# 2CH_PM_Simulator.net
KiCad netlist of a schematic drawn in Altium Designer
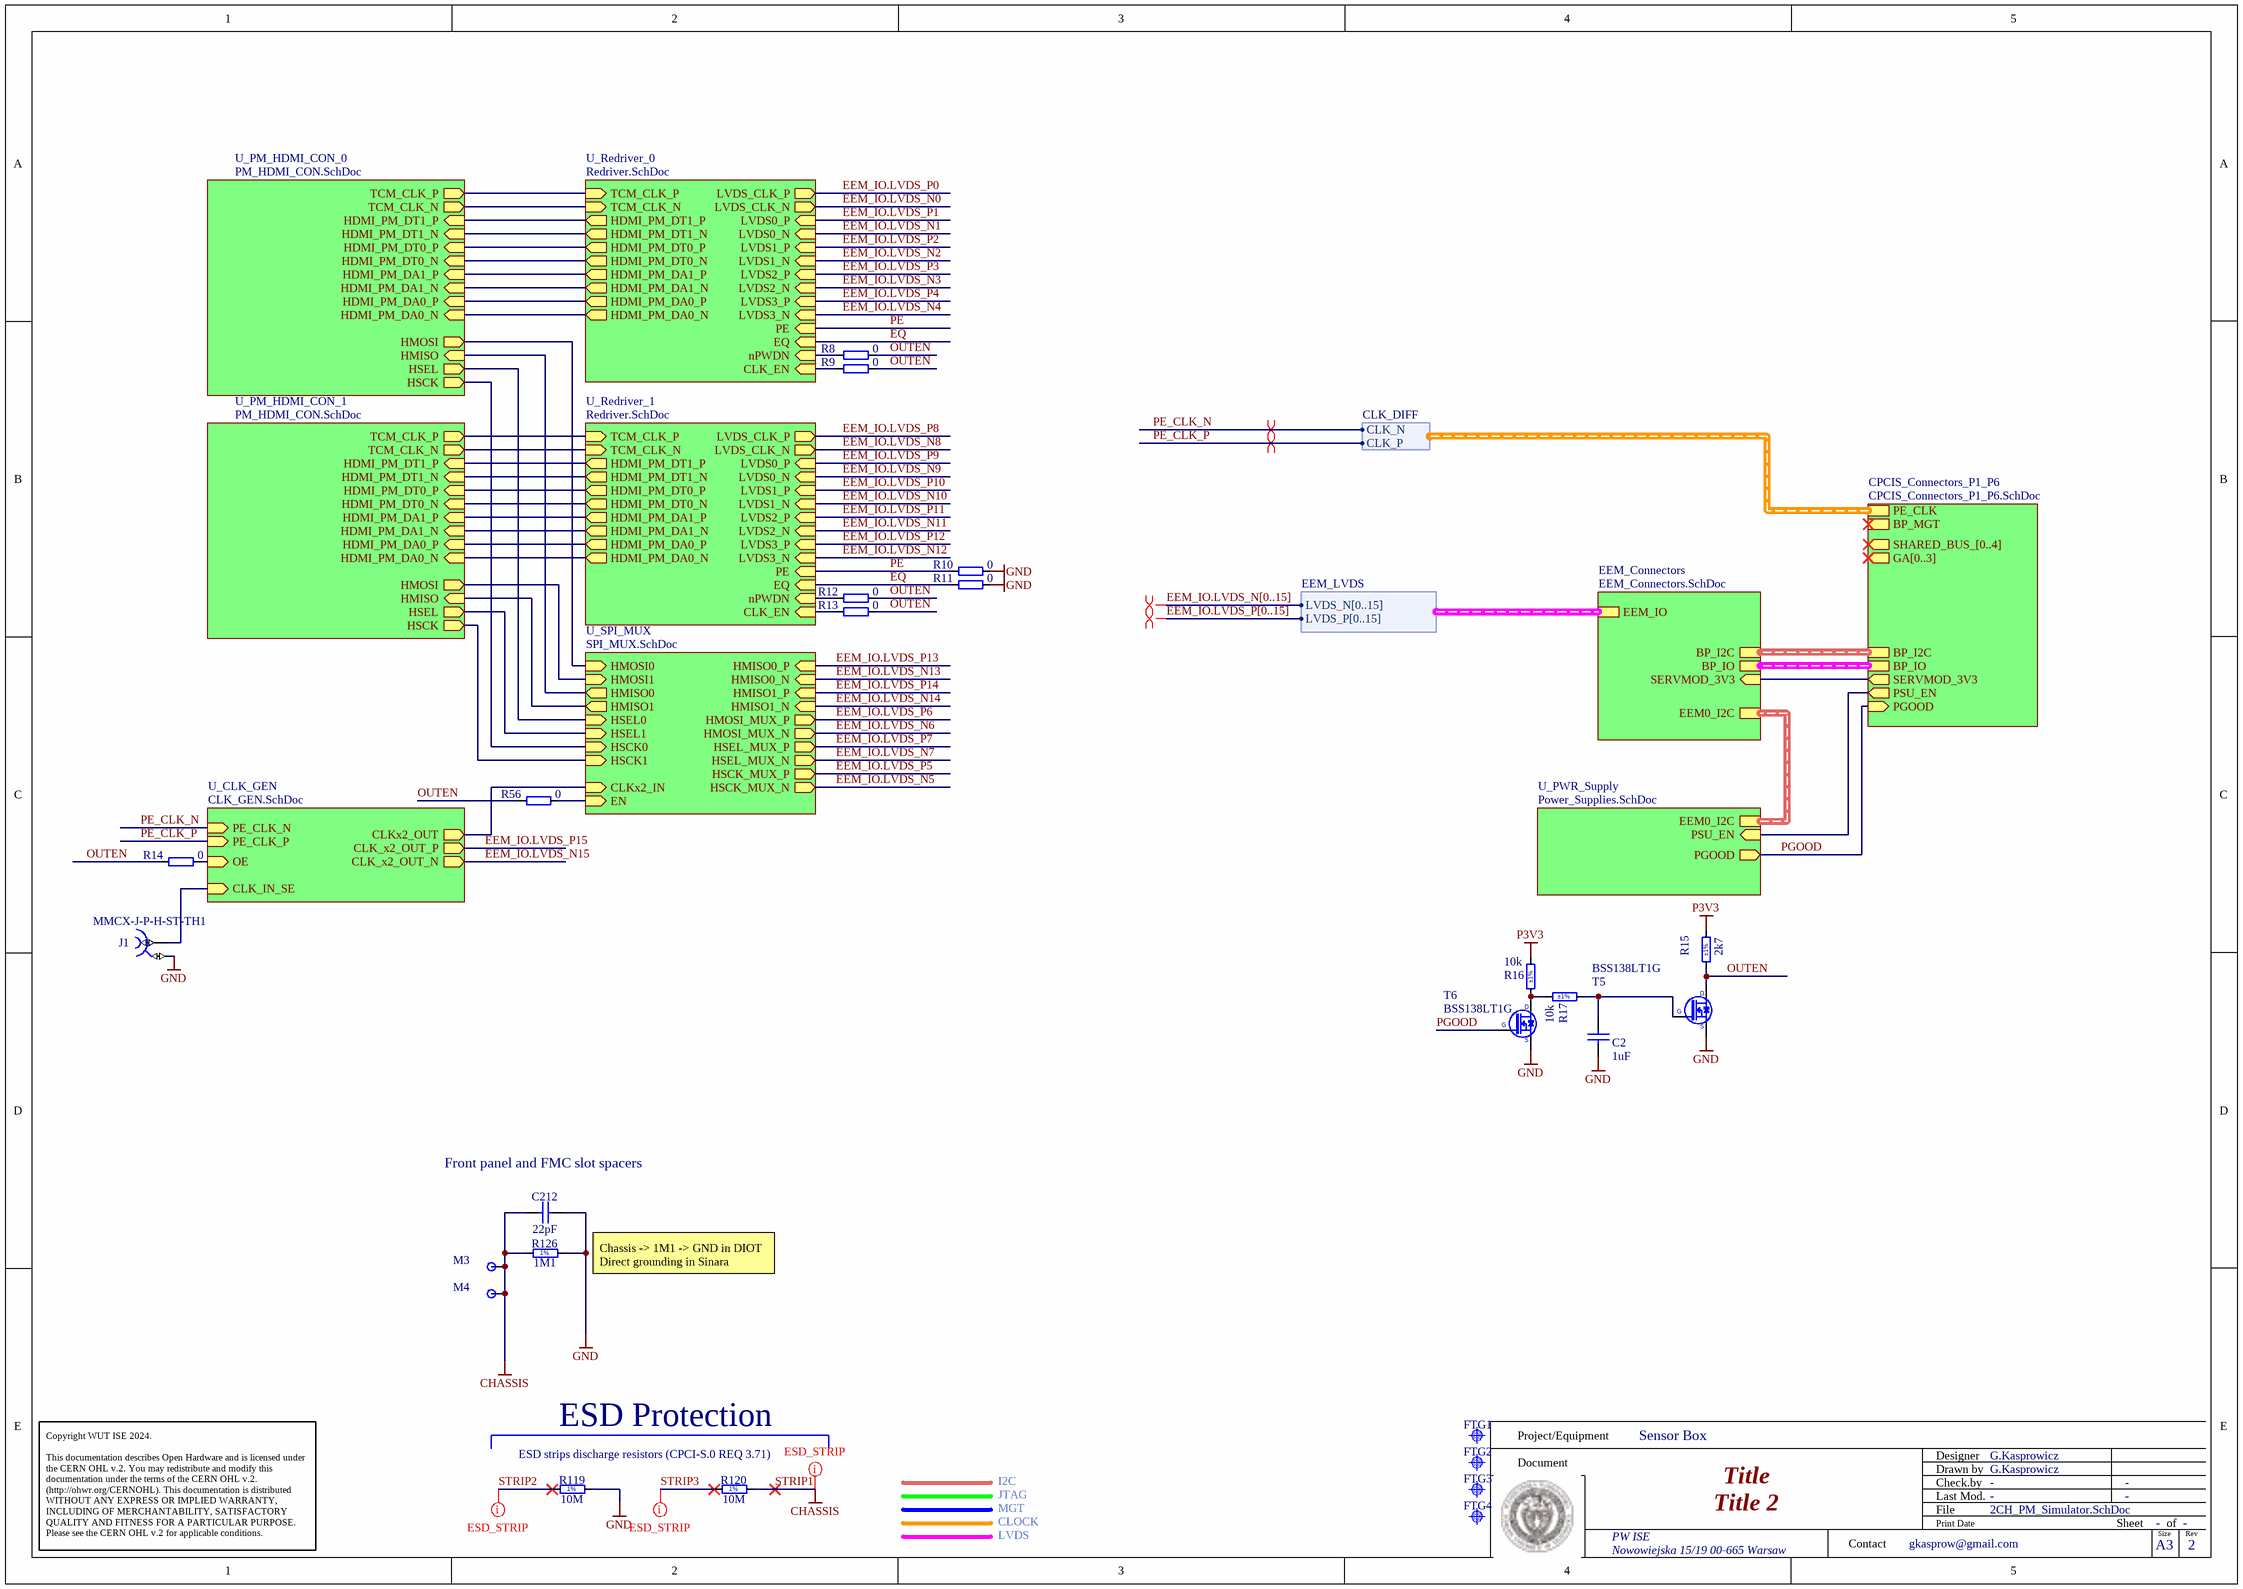
[diagram p0: 2CH_PM_Simulator.SchDoc]

(export (version "E")
  (design (tool "Eeschema 10.0.6"))
  (components
    (comp (ref "C2")
      (value "1uF")
      (footprint "CAPC1608X87N")
      (description "Non-polarised capacitor")
      (fields
        (field (name "PART NUMBER") "CC0603_1UF_25V_10%_X7R")
        (field (name "VOLTAGE") "25V")
        (field (name "AUTHOR") "CERN DEM JLC")
      )
      (libsource (lib "Capacitors") (part "Capacitor - non polarized"))
    )
    (comp (ref "C212")
      (value "22pF")
      (footprint "CAPC1005X55N")
      (description "Non-polarised capacitor")
      (fields
        (field (name "PART NUMBER") "CC0402_22PF_50V_5%_C0G")
        (field (name "VOLTAGE") "50V")
        (field (name "AUTHOR") "CERN DEM JLC")
      )
      (libsource (lib "Capacitors") (part "Capacitor - non polarized"))
    )
    (comp (ref "FTG1")
      (value "Use only in PCB")
      (footprint "FIDUCIAL_TOP_C100-200")
      (description "Fiducial Target")
      (fields (field (name "PART NUMBER") "FIDUCIAL_TARGET_C100-200") (field (name "AUTHOR") "CERN DEM JLC"))
      (libsource (lib "Eletro-mechanical") (part "Fiducial Target"))
    )
    (comp (ref "FTG2")
      (value "Use only in PCB")
      (footprint "FIDUCIAL_TOP_S100-200")
      (description "Fiducial Target")
      (fields (field (name "PART NUMBER") "FIDUCIAL_TARGET_S100-200") (field (name "AUTHOR") "CERN DEM JLC"))
      (libsource (lib "Eletro-mechanical") (part "Fiducial Target"))
    )
    (comp (ref "FTG3")
      (value "Use only in PCB")
      (footprint "FIDUCIAL_TOP_S100-200")
      (description "Fiducial Target")
      (fields (field (name "PART NUMBER") "FIDUCIAL_TARGET_S100-200") (field (name "AUTHOR") "CERN DEM JLC"))
      (libsource (lib "Eletro-mechanical") (part "Fiducial Target"))
    )
    (comp (ref "FTG4")
      (value "Use only in PCB")
      (footprint "FIDUCIAL_TOP_S100-200")
      (description "Fiducial Target")
      (fields (field (name "PART NUMBER") "FIDUCIAL_TARGET_S100-200") (field (name "AUTHOR") "CERN DEM JLC"))
      (libsource (lib "Eletro-mechanical") (part "Fiducial Target"))
    )
    (comp (ref "J1")
      (value "Coax_1Female_1Shield")
      (footprint "SAMTEC_MMCX-J-P-H-ST-TH1")
      (fields
        (field (name "PART NUMBER") "SAMTEC_MMCX-J-P-H-ST-TH1")
        (field (name "MANUFACTURER") "SAMTEC")
        (field (name "MANUFACTURER PART NUMBER") "MMCX-J-P-H-ST-TH1")
        (field (name "AUTHOR") "CERN DEM JLC")
      )
      (libsource (lib "Connectors") (part "Coax_1Female_1Shield"))
    )
    (comp (ref "M3")
      (value "Plated Hole")
      (footprint "MTG300_600")
      (description "Single Terminal Socket")
      (fields (field (name "PART NUMBER") "PLATED_HOLE3.0_PAD6.0") (field (name "AUTHOR") "CERN DEM JLC"))
      (libsource (lib "Eletro-mechanical") (part "Single Terminal Socket"))
    )
    (comp (ref "M4")
      (value "Plated Hole")
      (footprint "MTG300_600")
      (description "Single Terminal Socket")
      (fields (field (name "PART NUMBER") "PLATED_HOLE3.0_PAD6.0") (field (name "AUTHOR") "CERN DEM JLC"))
      (libsource (lib "Eletro-mechanical") (part "Single Terminal Socket"))
    )
    (comp (ref "R8")
      (value "0")
      (footprint "RESC1005X40N")
      (description "Resistor")
      (fields
        (field (name "PART NUMBER") "R0402_0R_JUMPER")
        (field (name "MANUFACTURER") "GENERIC")
        (field (name "AUTHOR") "CERN DEM JLC")
      )
      (libsource (lib "Resistors") (part "Resistor"))
    )
    (comp (ref "R9")
      (value "0")
      (footprint "RESC1005X40N")
      (description "Resistor")
      (fields
        (field (name "PART NUMBER") "R0402_0R_JUMPER")
        (field (name "MANUFACTURER") "GENERIC")
        (field (name "AUTHOR") "CERN DEM JLC")
      )
      (libsource (lib "Resistors") (part "Resistor"))
    )
    (comp (ref "R10")
      (value "0")
      (footprint "RESC1005X40N")
      (description "Resistor")
      (fields
        (field (name "PART NUMBER") "R0402_0R_JUMPER")
        (field (name "MANUFACTURER") "GENERIC")
        (field (name "AUTHOR") "CERN DEM JLC")
      )
      (libsource (lib "Resistors") (part "Resistor"))
    )
    (comp (ref "R11")
      (value "0")
      (footprint "RESC1005X40N")
      (description "Resistor")
      (fields
        (field (name "PART NUMBER") "R0402_0R_JUMPER")
        (field (name "MANUFACTURER") "GENERIC")
        (field (name "AUTHOR") "CERN DEM JLC")
      )
      (libsource (lib "Resistors") (part "Resistor"))
    )
    (comp (ref "R12")
      (value "0")
      (footprint "RESC1005X40N")
      (description "Resistor")
      (fields
        (field (name "PART NUMBER") "R0402_0R_JUMPER")
        (field (name "MANUFACTURER") "GENERIC")
        (field (name "AUTHOR") "CERN DEM JLC")
      )
      (libsource (lib "Resistors") (part "Resistor"))
    )
    (comp (ref "R13")
      (value "0")
      (footprint "RESC1005X40N")
      (description "Resistor")
      (fields
        (field (name "PART NUMBER") "R0402_0R_JUMPER")
        (field (name "MANUFACTURER") "GENERIC")
        (field (name "AUTHOR") "CERN DEM JLC")
      )
      (libsource (lib "Resistors") (part "Resistor"))
    )
    (comp (ref "R14")
      (value "0")
      (footprint "RESC1005X40N")
      (description "Resistor")
      (fields
        (field (name "PART NUMBER") "R0402_0R_JUMPER")
        (field (name "MANUFACTURER") "GENERIC")
        (field (name "AUTHOR") "CERN DEM JLC")
      )
      (libsource (lib "Resistors") (part "Resistor"))
    )
    (comp (ref "R15")
      (value "2k7")
      (footprint "RESC1608X55N")
      (description "Resistor - 1%")
      (fields
        (field (name "TOLERANCE") "±1%")
        (field (name "PART NUMBER") "R0603_2K7_1%_0.1W_100PPM")
        (field (name "POWER") "0.1W")
        (field (name "AUTHOR") "CERN DEM JLC")
      )
      (libsource (lib "") (part "Resistor - 1%_1"))
    )
    (comp (ref "R16")
      (value "10k")
      (footprint "RESC1608X55N")
      (description "Resistor - 1%")
      (fields
        (field (name "TOLERANCE") "±1%")
        (field (name "PART NUMBER") "R0603_10K_1%_0.1W_100PPM")
        (field (name "POWER") "0.1W")
        (field (name "AUTHOR") "CERN DEM JLC")
      )
      (libsource (lib "") (part "Resistor - 1%_1"))
    )
    (comp (ref "R17")
      (value "10k")
      (footprint "RESC1608X55N")
      (description "Resistor - 1%")
      (fields
        (field (name "TOLERANCE") "±1%")
        (field (name "PART NUMBER") "R0603_10K_1%_0.1W_100PPM")
        (field (name "POWER") "0.1W")
        (field (name "AUTHOR") "CERN DEM JLC")
      )
      (libsource (lib "") (part "Resistor - 1%_1"))
    )
    (comp (ref "R56")
      (value "0")
      (footprint "RESC1005X40N")
      (description "Resistor")
      (fields
        (field (name "PART NUMBER") "R0402_0R_JUMPER")
        (field (name "MANUFACTURER") "GENERIC")
        (field (name "AUTHOR") "CERN DEM JLC")
      )
      (libsource (lib "Resistors") (part "Resistor"))
    )
    (comp (ref "R119")
      (value "10M")
      (footprint "RESC2113X55N")
      (description "Resistor - 1%")
      (fields
        (field (name "PART NUMBER") "R0805_10M_1%_0.125W_100PPM_VISHAY_CRCW e3")
        (field (name "POWER") "0.125W")
        (field (name "AUTHOR") "CERN DEM BC")
      )
      (libsource (lib "Resistors") (part "Resistor - 1%"))
    )
    (comp (ref "R120")
      (value "10M")
      (footprint "RESC2113X55N")
      (description "Resistor - 1%")
      (fields
        (field (name "PART NUMBER") "R0805_10M_1%_0.125W_100PPM_VISHAY_CRCW e3")
        (field (name "POWER") "0.125W")
        (field (name "AUTHOR") "CERN DEM BC")
      )
      (libsource (lib "Resistors") (part "Resistor - 1%"))
    )
    (comp (ref "R126")
      (value "1M1")
      (footprint "RESC2012X60N")
      (description "Resistor - 1%")
      (fields
        (field (name "PART NUMBER") "R0805_1M1_1%_0.125W_100PPM")
        (field (name "MANUFACTURER") "GENERIC")
        (field (name "AUTHOR") "CERN DEM JLC")
      )
      (libsource (lib "Resistors") (part "Resistor - 1%"))
    )
    (comp (ref "T5")
      (value "BSS138LT1G")
      (footprint "SOT95P240X110-3N")
      (description "N-CHANNEL MOSFET WITH DIODE")
      (fields
        (field (name "MANUFACTURER") "ON SEMICONDUCTOR")
        (field (name "MANUFACTURER PART NUMBER") "BSS138L")
        (field (name "AUTHOR") "CERN DEM JLC")
      )
      (libsource (lib "ICs And Semiconductors") (part "N-MOSFET-D 1G 2S 3D"))
    )
    (comp (ref "T6")
      (value "BSS138LT1G")
      (footprint "SOT95P240X110-3N")
      (description "N-CHANNEL MOSFET WITH DIODE")
      (fields
        (field (name "MANUFACTURER") "ON SEMICONDUCTOR")
        (field (name "MANUFACTURER PART NUMBER") "BSS138L")
        (field (name "AUTHOR") "CERN DEM JLC")
      )
      (libsource (lib "ICs And Semiconductors") (part "N-MOSFET-D 1G 2S 3D"))
    )
  )
  (nets
    (net (code "5") (name "/CLK_EN") (class "Default")
      (node (ref "R9") (pin "1") (pinfunction "1_1") (pintype "passive"))
    )
    (net (code "6") (name "/CLK_EN_1") (class "Default")
      (node (ref "R13") (pin "1") (pinfunction "1_1") (pintype "passive"))
    )
    (net (code "7") (name "/CLK_IN_SE") (class "Default")
      (node (ref "J1") (pin "1") (pinfunction "1_1") (pintype "bidirectional"))
    )
    (net (code "44") (name "/EN") (class "Default")
      (node (ref "R56") (pin "2") (pinfunction "2_2") (pintype "passive"))
    )
    (net (code "45") (name "/EQ") (class "Default")
      (node (ref "R11") (pin "1") (pinfunction "1_1") (pintype "passive"))
    )
    (net (code "71") (name "/OE") (class "Default")
      (node (ref "R14") (pin "2") (pinfunction "2_2") (pintype "passive"))
    )
    (net (code "72") (name "/OUTEN") (class "Default")
      (node (ref "R12") (pin "2") (pinfunction "2_2") (pintype "passive"))
      (node (ref "R13") (pin "2") (pinfunction "2_2") (pintype "passive"))
      (node (ref "R14") (pin "1") (pinfunction "1_1") (pintype "passive"))
      (node (ref "R15") (pin "1") (pinfunction "1_1") (pintype "passive"))
      (node (ref "R56") (pin "1") (pinfunction "1_1") (pintype "passive"))
      (node (ref "R8") (pin "2") (pinfunction "2_2") (pintype "passive"))
      (node (ref "R9") (pin "2") (pinfunction "2_2") (pintype "passive"))
      (node (ref "T5") (pin "3") (pinfunction "D_3") (pintype "passive"))
    )
    (net (code "73") (name "/PE") (class "Default")
      (node (ref "R10") (pin "1") (pinfunction "1_1") (pintype "passive"))
    )
    (net (code "76") (name "/PGOOD") (class "Default")
      (node (ref "T6") (pin "1") (pinfunction "G_1") (pintype "passive"))
    )
    (net (code "81") (name "/STRIP2") (class "Default")
      (node (ref "R119") (pin "1") (pinfunction "1_1") (pintype "passive+no_connect"))
    )
    (net (code "82") (name "/STRIP3") (class "Default")
      (node (ref "R120") (pin "1") (pinfunction "1_1") (pintype "passive+no_connect"))
    )
    (net (code "87") (name "/nPWDN") (class "Default")
      (node (ref "R8") (pin "1") (pinfunction "1_1") (pintype "passive"))
    )
    (net (code "88") (name "/nPWDN_1") (class "Default")
      (node (ref "R12") (pin "1") (pinfunction "1_1") (pintype "passive"))
    )
    (net (code "90") (name "CHASSIS") (class "Default")
      (node (ref "C212") (pin "1") (pinfunction "1_1") (pintype "passive"))
      (node (ref "M3") (pin "1") (pinfunction "1_1") (pintype "bidirectional"))
      (node (ref "M4") (pin "1") (pinfunction "1_1") (pintype "bidirectional"))
      (node (ref "R120") (pin "2") (pinfunction "2_2") (pintype "passive"))
      (node (ref "R126") (pin "1") (pinfunction "1_1") (pintype "passive"))
    )
    (net (code "91") (name "GND") (class "Default")
      (node (ref "C2") (pin "1") (pinfunction "1_1") (pintype "passive"))
      (node (ref "C212") (pin "2") (pinfunction "2_2") (pintype "passive"))
      (node (ref "J1") (pin "2") (pinfunction "2_2") (pintype "bidirectional"))
      (node (ref "R10") (pin "2") (pinfunction "2_2") (pintype "passive"))
      (node (ref "R11") (pin "2") (pinfunction "2_2") (pintype "passive"))
      (node (ref "R119") (pin "2") (pinfunction "2_2") (pintype "passive"))
      (node (ref "R126") (pin "2") (pinfunction "2_2") (pintype "passive"))
      (node (ref "T5") (pin "2") (pinfunction "S_2") (pintype "passive"))
      (node (ref "T6") (pin "2") (pinfunction "S_2") (pintype "passive"))
    )
    (net (code "92") (name "Net-(T5-G)") (class "Default")
      (node (ref "C2") (pin "2") (pinfunction "2_2") (pintype "passive"))
      (node (ref "R17") (pin "1") (pinfunction "1_1") (pintype "passive"))
      (node (ref "T5") (pin "1") (pinfunction "G_1") (pintype "passive"))
    )
    (net (code "93") (name "Net-(T6-D)") (class "Default")
      (node (ref "R16") (pin "1") (pinfunction "1_1") (pintype "passive"))
      (node (ref "R17") (pin "2") (pinfunction "2_2") (pintype "passive"))
      (node (ref "T6") (pin "3") (pinfunction "D_3") (pintype "passive"))
    )
    (net (code "94") (name "P3V3") (class "Default")
      (node (ref "R15") (pin "2") (pinfunction "2_2") (pintype "passive"))
      (node (ref "R16") (pin "2") (pinfunction "2_2") (pintype "passive"))
    )
  )
)
